# AVR85_test.net
KiCad netlist of a schematic drawn in EAGLE
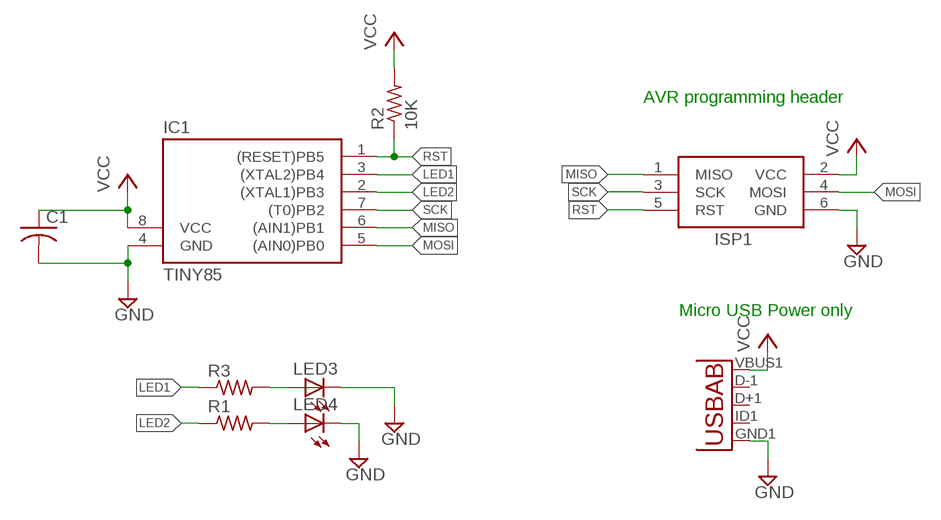
[diagram p0: schematic, sheet 1]

(export (version "E")
  (design (tool "Eeschema 10.0.6"))
  (components
    (comp (ref "C1")
      (value "C-USC0805")
      (footprint "eagle-import:C0805")
      (libsource (lib "eagle-import") (part "C-USC0805"))
    )
    (comp (ref "IC1")
      (value "TINY85")
      (footprint "eagle-import:SOIC8")
      (libsource (lib "eagle-import") (part "TINY10S"))
    )
    (comp (ref "ISP1")
      (value "AVRISP-6")
      (footprint "eagle-import:AVRISP")
      (libsource (lib "eagle-import") (part "AVRISP-6"))
    )
    (comp (ref "LED3")
      (value "LEDCHIPLED_0805")
      (footprint "eagle-import:CHIPLED_0805")
      (libsource (lib "eagle-import") (part "LEDCHIPLED_0805"))
    )
    (comp (ref "LED4")
      (value "LEDCHIPLED_0805")
      (footprint "eagle-import:CHIPLED_0805")
      (libsource (lib "eagle-import") (part "LEDCHIPLED_0805"))
    )
    (comp (ref "R1")
      (value "R-US_R0805")
      (footprint "eagle-import:R0805")
      (libsource (lib "eagle-import") (part "R-US_R0805"))
    )
    (comp (ref "R2")
      (value "10K")
      (footprint "eagle-import:R0805")
      (libsource (lib "eagle-import") (part "R-US_R0805"))
    )
    (comp (ref "R3")
      (value "R-US_R0805")
      (footprint "eagle-import:R0805")
      (libsource (lib "eagle-import") (part "R-US_R0805"))
    )
    (comp (ref "U1")
      (value "USB\"\"")
      (footprint "eagle-import:USB-MICRO-SMD")
      (libsource (lib "eagle-import") (part "USB{dblquote}{dblquote}"))
    )
  )
  (nets
    (net (code "1") (name "GND") (class "Default")
      (node (ref "C1") (pin "2") (pinfunction "2_2") (pintype "passive"))
      (node (ref "IC1") (pin "4") (pinfunction "GND_4") (pintype "power_in"))
      (node (ref "ISP1") (pin "6") (pinfunction "GND_6") (pintype "power_in"))
      (node (ref "LED3") (pin "C") (pinfunction "C_C") (pintype "passive"))
      (node (ref "LED4") (pin "C") (pinfunction "C_C") (pintype "passive"))
      (node (ref "U1") (pin "GND1") (pinfunction "GND_GND1") (pintype "bidirectional"))
    )
    (net (code "2") (name "LED1") (class "Default")
      (node (ref "IC1") (pin "3") (pinfunction "(XTAL2)PB4_3") (pintype "bidirectional"))
      (node (ref "R3") (pin "1") (pinfunction "1_1") (pintype "passive"))
    )
    (net (code "3") (name "LED2") (class "Default")
      (node (ref "IC1") (pin "2") (pinfunction "(XTAL1)PB3_2") (pintype "bidirectional"))
      (node (ref "R1") (pin "1") (pinfunction "1_1") (pintype "passive"))
    )
    (net (code "4") (name "MISO") (class "Default")
      (node (ref "IC1") (pin "6") (pinfunction "(AIN1)PB1_6") (pintype "bidirectional"))
      (node (ref "ISP1") (pin "1") (pinfunction "MISO_1") (pintype "input"))
    )
    (net (code "5") (name "MOSI") (class "Default")
      (node (ref "IC1") (pin "5") (pinfunction "(AIN0)PB0_5") (pintype "bidirectional"))
      (node (ref "ISP1") (pin "4") (pinfunction "MOSI_4") (pintype "output"))
    )
    (net (code "6") (name "Net-(LED3-PadA)") (class "Default")
      (node (ref "LED3") (pin "A") (pinfunction "A_A") (pintype "passive"))
      (node (ref "R3") (pin "2") (pinfunction "2_2") (pintype "passive"))
    )
    (net (code "7") (name "Net-(LED4-PadA)") (class "Default")
      (node (ref "LED4") (pin "A") (pinfunction "A_A") (pintype "passive"))
      (node (ref "R1") (pin "2") (pinfunction "2_2") (pintype "passive"))
    )
    (net (code "8") (name "RST") (class "Default")
      (node (ref "IC1") (pin "1") (pinfunction "(RESET)PB5_1") (pintype "bidirectional"))
      (node (ref "ISP1") (pin "5") (pinfunction "RST_5") (pintype "output"))
      (node (ref "R2") (pin "1") (pinfunction "1_1") (pintype "passive"))
    )
    (net (code "9") (name "SCK") (class "Default")
      (node (ref "IC1") (pin "7") (pinfunction "(T0)PB2_7") (pintype "bidirectional"))
      (node (ref "ISP1") (pin "3") (pinfunction "SCK_3") (pintype "output"))
    )
    (net (code "10") (name "VCC") (class "Default")
      (node (ref "C1") (pin "1") (pinfunction "1_1") (pintype "passive"))
      (node (ref "IC1") (pin "8") (pinfunction "VCC_8") (pintype "power_in"))
      (node (ref "ISP1") (pin "2") (pinfunction "VCC_2") (pintype "power_in"))
      (node (ref "R2") (pin "2") (pinfunction "2_2") (pintype "passive"))
      (node (ref "U1") (pin "VBUS1") (pinfunction "VBUS_VBUS1") (pintype "bidirectional"))
    )
    (net (code "11") (name "unconnected-(U1-D+-PadD+1)") (class "Default")
      (node (ref "U1") (pin "D+1") (pinfunction "D+_D+1") (pintype "bidirectional"))
    )
    (net (code "12") (name "unconnected-(U1-D--PadD-1)") (class "Default")
      (node (ref "U1") (pin "D-1") (pinfunction "D-_D-1") (pintype "bidirectional"))
    )
    (net (code "13") (name "unconnected-(U1-USBID-PadID1)") (class "Default")
      (node (ref "U1") (pin "ID1") (pinfunction "USBID_ID1") (pintype "bidirectional"))
    )
  )
)
